# STeaMi-FP12-Capteur_interne.net
KiCad netlist of a schematic drawn in Altium Designer
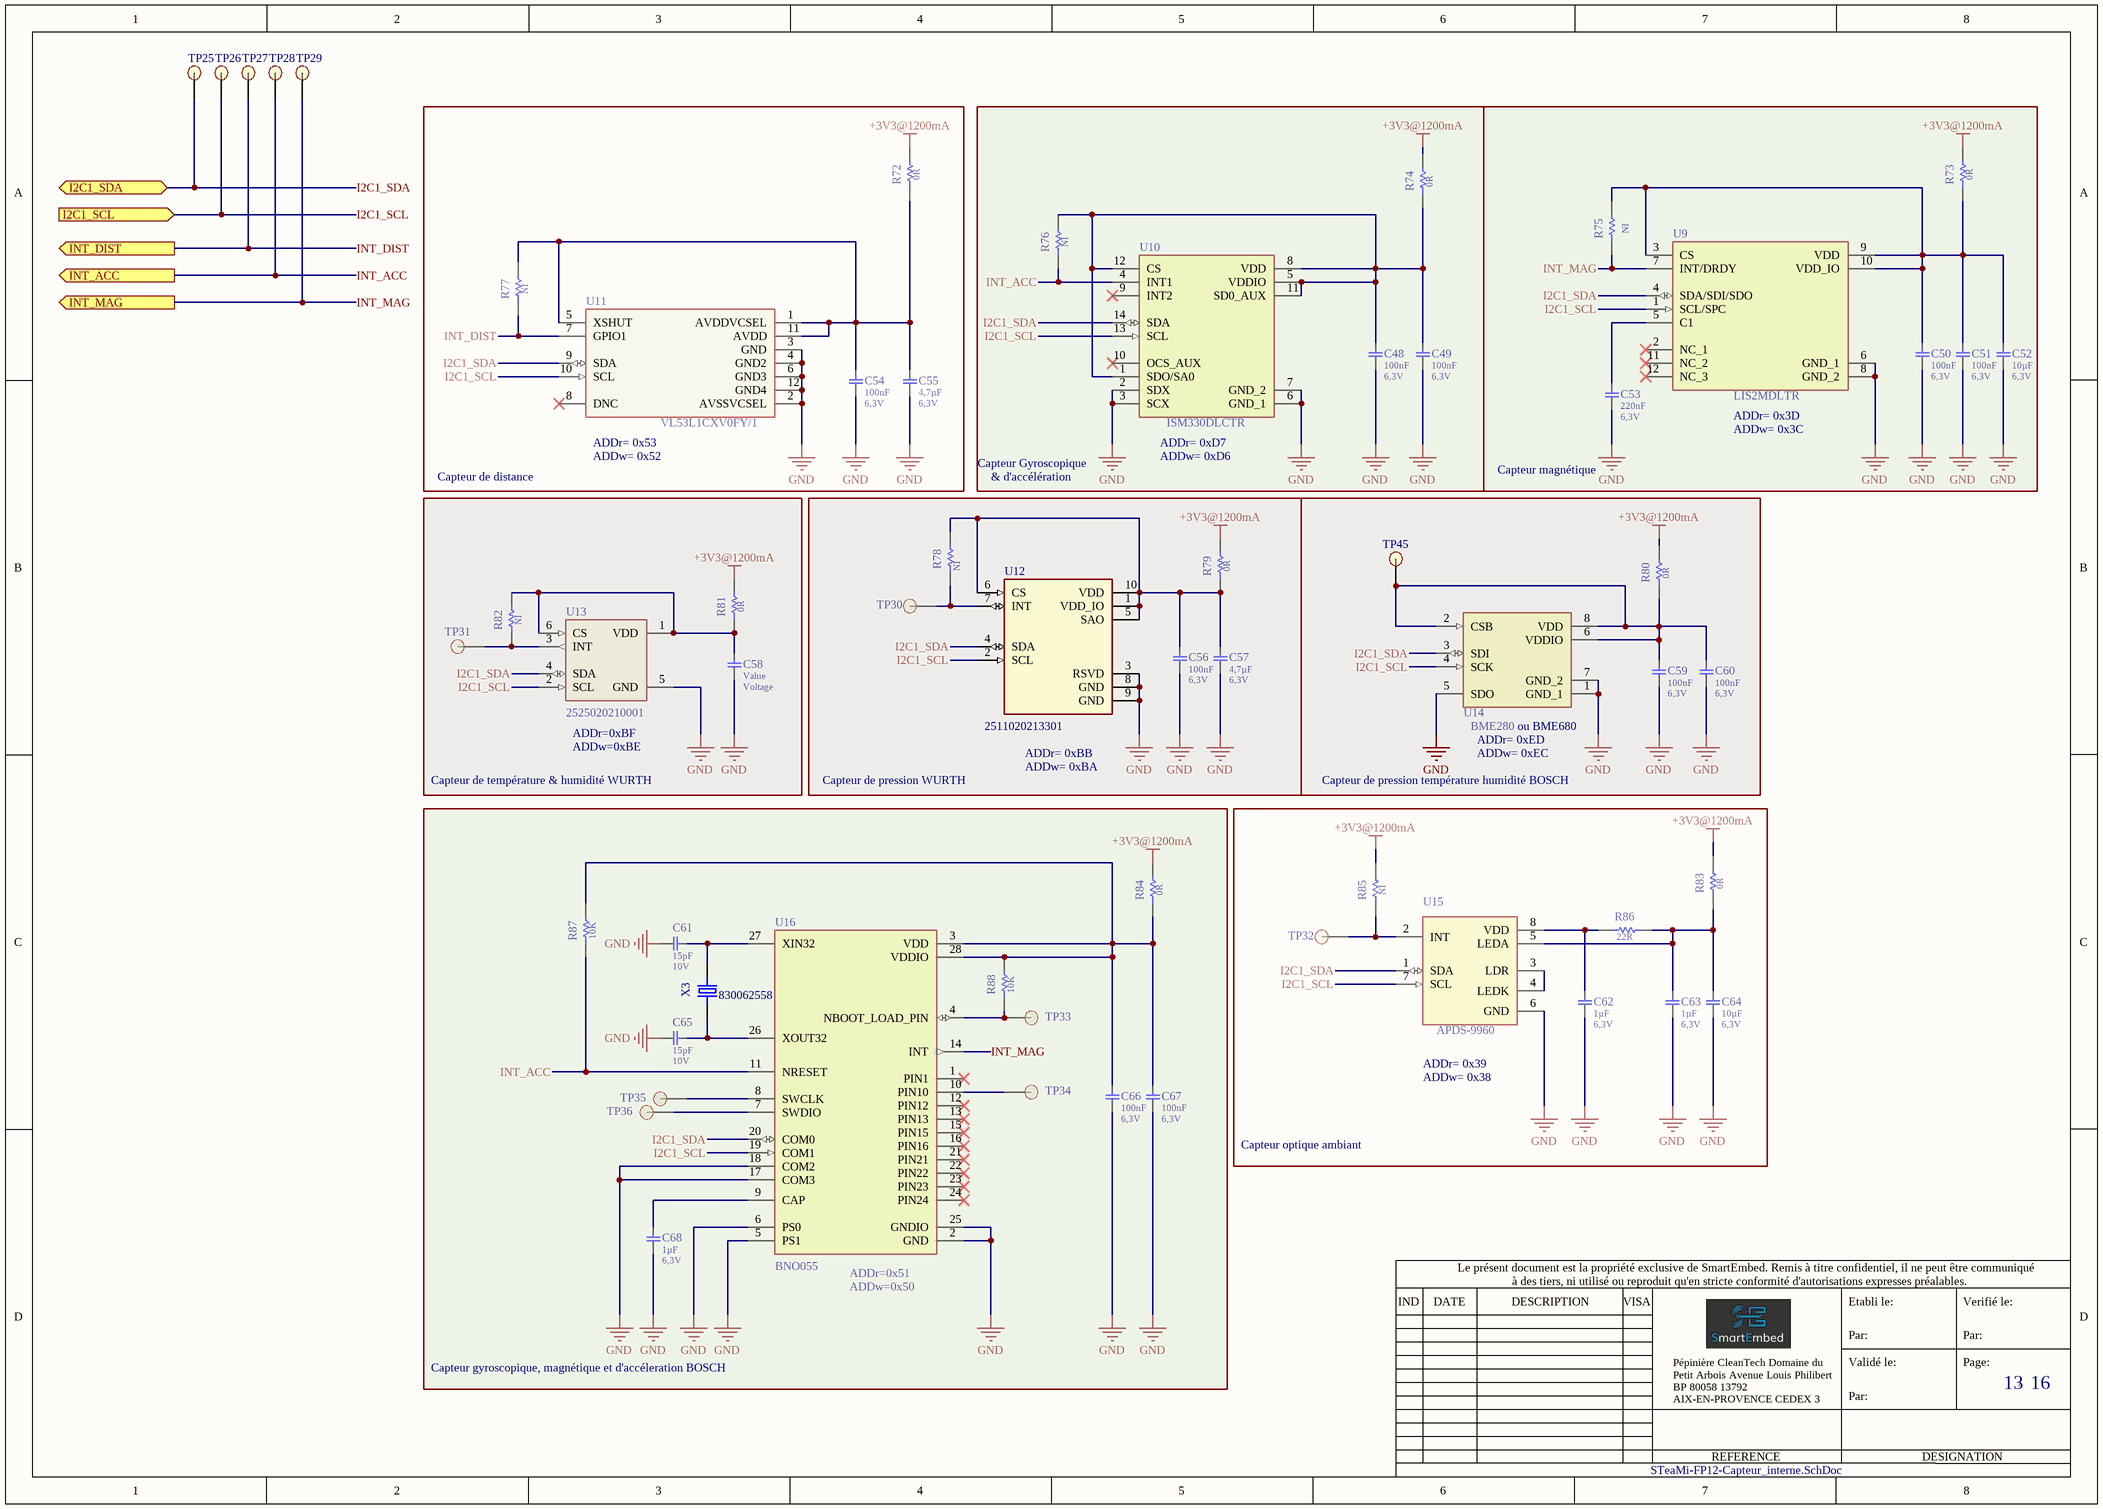
[diagram p0: STeaMi-FP12-Capteur_interne.SchDoc]

(export (version "E")
  (design (tool "Eeschema 10.0.6"))
  (components
    (comp (ref "C48")
      (value "~")
      (footprint "0402-CAP")
      (description "CAP CER 100nF 6,3V X5R 0402")
      (fields
        (field (name "MANUFACTURER") "Kyocera AVX")
        (field (name "MANUFACTURER PART NUMBER") "0402YD104KAT2A")
        (field (name "CAPACITANCE") "100nF")
        (field (name "VOLTAGE") "6,3V")
        (field (name "CREATED BY") "EAG")
        (field (name "CHECKED BY") "*")
      )
      (libsource (lib "ComponentDB") (part "CAP_SYMBOL"))
    )
    (comp (ref "C49")
      (value "~")
      (footprint "0402-CAP")
      (description "CAP CER 100nF 6,3V X5R 0402")
      (fields
        (field (name "MANUFACTURER") "Kyocera AVX")
        (field (name "MANUFACTURER PART NUMBER") "0402YD104KAT2A")
        (field (name "CAPACITANCE") "100nF")
        (field (name "VOLTAGE") "6,3V")
        (field (name "CREATED BY") "EAG")
        (field (name "CHECKED BY") "*")
      )
      (libsource (lib "ComponentDB") (part "CAP_SYMBOL"))
    )
    (comp (ref "C50")
      (value "~")
      (footprint "0402-CAP")
      (description "CAP CER 100nF 6,3V X5R 0402")
      (fields
        (field (name "MANUFACTURER") "Kyocera AVX")
        (field (name "MANUFACTURER PART NUMBER") "0402YD104KAT2A")
        (field (name "CAPACITANCE") "100nF")
        (field (name "VOLTAGE") "6,3V")
        (field (name "CREATED BY") "EAG")
        (field (name "CHECKED BY") "*")
      )
      (libsource (lib "ComponentDB") (part "CAP_SYMBOL"))
    )
    (comp (ref "C51")
      (value "~")
      (footprint "0402-CAP")
      (description "CAP CER 100nF 6,3V X5R 0402")
      (fields
        (field (name "MANUFACTURER") "Kyocera AVX")
        (field (name "MANUFACTURER PART NUMBER") "0402YD104KAT2A")
        (field (name "CAPACITANCE") "100nF")
        (field (name "VOLTAGE") "6,3V")
        (field (name "CREATED BY") "EAG")
        (field (name "CHECKED BY") "*")
      )
      (libsource (lib "ComponentDB") (part "CAP_SYMBOL"))
    )
    (comp (ref "C52")
      (value "~")
      (footprint "0402-CAP")
      (description "CAP CER 10µF 6,3V X5R 0402")
      (fields
        (field (name "MANUFACTURER") "Murata")
        (field (name "MANUFACTURER PART NUMBER") "GRM155R60J106ME15D")
        (field (name "CAPACITANCE") "10µF")
        (field (name "VOLTAGE") "6,3V")
        (field (name "CREATED BY") "EAG")
        (field (name "CHECKED BY") "*")
      )
      (libsource (lib "ComponentDB") (part "CAP_SYMBOL"))
    )
    (comp (ref "C53")
      (value "~")
      (footprint "0603-CAP-Small")
      (description "CAP CER 220nF 6,3V X7R 0603")
      (fields
        (field (name "CAPACITANCE") "220nF")
        (field (name "VOLTAGE") "6,3V")
        (field (name "PART NUMBER") "220nF-10%-6,3V-X7R-0603")
        (field (name "CREATED BY") "EAG")
        (field (name "CHECKED BY") "*")
      )
      (libsource (lib "ComponentDB") (part "CAP_SYMBOL"))
    )
    (comp (ref "C54")
      (value "~")
      (footprint "0402-CAP")
      (description "CAP CER 100nF 6,3V X5R 0402")
      (fields
        (field (name "MANUFACTURER") "Kyocera AVX")
        (field (name "MANUFACTURER PART NUMBER") "0402YD104KAT2A")
        (field (name "CAPACITANCE") "100nF")
        (field (name "VOLTAGE") "6,3V")
        (field (name "CREATED BY") "EAG")
        (field (name "CHECKED BY") "*")
      )
      (libsource (lib "ComponentDB") (part "CAP_SYMBOL"))
    )
    (comp (ref "C55")
      (value "~")
      (footprint "0402-CAP")
      (description "CAP CER 4,7µF 6,3V X5R 0402")
      (fields
        (field (name "CAPACITANCE") "4,7µF")
        (field (name "VOLTAGE") "6,3V")
        (field (name "PART NUMBER") "4,7µF-20%-6,3V-X5R-0402")
        (field (name "CREATED BY") "EAG")
        (field (name "CHECKED BY") "*")
      )
      (libsource (lib "ComponentDB") (part "CAP_SYMBOL"))
    )
    (comp (ref "C56")
      (value "~")
      (footprint "0402-CAP")
      (description "CAP CER 100nF 6,3V X5R 0402")
      (fields
        (field (name "MANUFACTURER") "Kyocera AVX")
        (field (name "MANUFACTURER PART NUMBER") "0402YD104KAT2A")
        (field (name "CAPACITANCE") "100nF")
        (field (name "VOLTAGE") "6,3V")
        (field (name "CREATED BY") "EAG")
        (field (name "CHECKED BY") "*")
      )
      (libsource (lib "ComponentDB") (part "CAP_SYMBOL"))
    )
    (comp (ref "C57")
      (value "~")
      (footprint "0402-CAP")
      (description "CAP CER 4,7µF 6,3V X5R 0402")
      (fields
        (field (name "CAPACITANCE") "4,7µF")
        (field (name "VOLTAGE") "6,3V")
        (field (name "PART NUMBER") "4,7µF-20%-6,3V-X5R-0402")
        (field (name "CREATED BY") "EAG")
        (field (name "CHECKED BY") "*")
      )
      (libsource (lib "ComponentDB") (part "CAP_SYMBOL"))
    )
    (comp (ref "C58")
      (value "~")
      (footprint "0402-CAP")
      (description "CAP CER 100nF 6,3V X5R 0402")
      (fields
        (field (name "CAPACITANCE") "Value")
        (field (name "VOLTAGE") "Voltage")
        (field (name "PART NUMBER") "100nF-10%-6,3V-X5R-0402")
        (field (name "CREATED BY") "*")
        (field (name "CHECKED BY") "*")
      )
      (libsource (lib "ComponentDB") (part "CAP_SYMBOL"))
    )
    (comp (ref "C59")
      (value "~")
      (footprint "0402-CAP")
      (description "CAP CER 100nF 6,3V X5R 0402")
      (fields
        (field (name "MANUFACTURER") "Kyocera AVX")
        (field (name "MANUFACTURER PART NUMBER") "0402YD104KAT2A")
        (field (name "CAPACITANCE") "100nF")
        (field (name "VOLTAGE") "6,3V")
        (field (name "CREATED BY") "EAG")
        (field (name "CHECKED BY") "*")
      )
      (libsource (lib "ComponentDB") (part "CAP_SYMBOL"))
    )
    (comp (ref "C60")
      (value "~")
      (footprint "0402-CAP")
      (description "CAP CER 100nF 6,3V X5R 0402")
      (fields
        (field (name "MANUFACTURER") "Kyocera AVX")
        (field (name "MANUFACTURER PART NUMBER") "0402YD104KAT2A")
        (field (name "CAPACITANCE") "100nF")
        (field (name "VOLTAGE") "6,3V")
        (field (name "CREATED BY") "EAG")
        (field (name "CHECKED BY") "*")
      )
      (libsource (lib "ComponentDB") (part "CAP_SYMBOL"))
    )
    (comp (ref "C61")
      (value "~")
      (footprint "0402-CAP")
      (description "CAP CER 15pF 10V C0G 0402")
      (fields
        (field (name "MANUFACTURER") "KEMET")
        (field (name "MANUFACTURER PART NUMBER") "C0402C150J8HACTU")
        (field (name "CAPACITANCE") "15pF")
        (field (name "VOLTAGE") "10V")
        (field (name "CREATED BY") "EAG")
        (field (name "CHECKED BY") "*")
      )
      (libsource (lib "ComponentDB") (part "CAP_SYMBOL"))
    )
    (comp (ref "C62")
      (value "~")
      (footprint "0402-CAP")
      (description "CAP CER 1µF 6,3V X5R 0402")
      (fields
        (field (name "MANUFACTURER") "Taiyo Yuden")
        (field (name "MANUFACTURER PART NUMBER") "JMK105BJ105KV-F")
        (field (name "CAPACITANCE") "1µF")
        (field (name "VOLTAGE") "6,3V")
        (field (name "CREATED BY") "EAG")
        (field (name "CHECKED BY") "*")
      )
      (libsource (lib "ComponentDB") (part "CAP_SYMBOL"))
    )
    (comp (ref "C63")
      (value "~")
      (footprint "0402-CAP")
      (description "CAP CER 1µF 6,3V X5R 0402")
      (fields
        (field (name "MANUFACTURER") "Taiyo Yuden")
        (field (name "MANUFACTURER PART NUMBER") "JMK105BJ105KV-F")
        (field (name "CAPACITANCE") "1µF")
        (field (name "VOLTAGE") "6,3V")
        (field (name "CREATED BY") "EAG")
        (field (name "CHECKED BY") "*")
      )
      (libsource (lib "ComponentDB") (part "CAP_SYMBOL"))
    )
    (comp (ref "C64")
      (value "~")
      (footprint "0402-CAP")
      (description "CAP CER 10µF 6,3V X5R 0402")
      (fields
        (field (name "MANUFACTURER") "Murata")
        (field (name "MANUFACTURER PART NUMBER") "GRM155R60J106ME15D")
        (field (name "CAPACITANCE") "10µF")
        (field (name "VOLTAGE") "6,3V")
        (field (name "CREATED BY") "EAG")
        (field (name "CHECKED BY") "*")
      )
      (libsource (lib "ComponentDB") (part "CAP_SYMBOL"))
    )
    (comp (ref "C65")
      (value "~")
      (footprint "0402-CAP")
      (description "CAP CER 15pF 10V C0G 0402")
      (fields
        (field (name "MANUFACTURER") "KEMET")
        (field (name "MANUFACTURER PART NUMBER") "C0402C150J8HACTU")
        (field (name "CAPACITANCE") "15pF")
        (field (name "VOLTAGE") "10V")
        (field (name "CREATED BY") "EAG")
        (field (name "CHECKED BY") "*")
      )
      (libsource (lib "ComponentDB") (part "CAP_SYMBOL"))
    )
    (comp (ref "C66")
      (value "~")
      (footprint "0402-CAP")
      (description "CAP CER 100nF 6,3V X5R 0402")
      (fields
        (field (name "MANUFACTURER") "Kyocera AVX")
        (field (name "MANUFACTURER PART NUMBER") "0402YD104KAT2A")
        (field (name "CAPACITANCE") "100nF")
        (field (name "VOLTAGE") "6,3V")
        (field (name "CREATED BY") "EAG")
        (field (name "CHECKED BY") "*")
      )
      (libsource (lib "ComponentDB") (part "CAP_SYMBOL"))
    )
    (comp (ref "C67")
      (value "~")
      (footprint "0402-CAP")
      (description "CAP CER 100nF 6,3V X5R 0402")
      (fields
        (field (name "MANUFACTURER") "Kyocera AVX")
        (field (name "MANUFACTURER PART NUMBER") "0402YD104KAT2A")
        (field (name "CAPACITANCE") "100nF")
        (field (name "VOLTAGE") "6,3V")
        (field (name "CREATED BY") "EAG")
        (field (name "CHECKED BY") "*")
      )
      (libsource (lib "ComponentDB") (part "CAP_SYMBOL"))
    )
    (comp (ref "C68")
      (value "~")
      (footprint "0402-CAP")
      (description "CAP CER 1µF 6,3V X5R 0402")
      (fields
        (field (name "MANUFACTURER") "Taiyo Yuden")
        (field (name "MANUFACTURER PART NUMBER") "JMK105BJ105KV-F")
        (field (name "CAPACITANCE") "1µF")
        (field (name "VOLTAGE") "6,3V")
        (field (name "CREATED BY") "EAG")
        (field (name "CHECKED BY") "*")
      )
      (libsource (lib "ComponentDB") (part "CAP_SYMBOL"))
    )
    (comp (ref "R72")
      (value "~")
      (footprint "RESC1005X40N_0402")
      (description "RES CMS 0R5%-0,0625W-0402")
      (fields
        (field (name "MANUFACTURER") "Yageo")
        (field (name "MANUFACTURER PART NUMBER") "RC0402JR-100RL")
        (field (name "RESISTANCE") "0R")
        (field (name "CREATED BY") "EAG")
      )
      (libsource (lib "ComponentDB") (part "RES_SYMBOL"))
    )
    (comp (ref "R73")
      (value "~")
      (footprint "RESC1005X40N_0402")
      (description "RES CMS 0R5%-0,0625W-0402")
      (fields
        (field (name "MANUFACTURER") "Yageo")
        (field (name "MANUFACTURER PART NUMBER") "RC0402JR-100RL")
        (field (name "RESISTANCE") "0R")
        (field (name "CREATED BY") "EAG")
      )
      (libsource (lib "ComponentDB") (part "RES_SYMBOL"))
    )
    (comp (ref "R74")
      (value "~")
      (footprint "RESC1005X40N_0402")
      (description "RES CMS 0R5%-0,0625W-0402")
      (fields
        (field (name "MANUFACTURER") "Yageo")
        (field (name "MANUFACTURER PART NUMBER") "RC0402JR-100RL")
        (field (name "RESISTANCE") "0R")
        (field (name "CREATED BY") "EAG")
      )
      (libsource (lib "ComponentDB") (part "RES_SYMBOL"))
    )
    (comp (ref "R75")
      (value "~")
      (footprint "RESC1005X40N_0402")
      (description "NI")
      (fields
        (field (name "POWER") "0,1")
        (field (name "RESISTANCE") "NI")
        (field (name "PART NUMBER") "NI-1%-0,1W-0603")
        (field (name "CREATED BY") "MSA")
      )
      (libsource (lib "ComponentDB") (part "RES_SYMBOL"))
    )
    (comp (ref "R76")
      (value "~")
      (footprint "RESC1005X40N_0402")
      (description "NI")
      (fields
        (field (name "POWER") "0,1")
        (field (name "RESISTANCE") "NI")
        (field (name "PART NUMBER") "NI-1%-0,1W-0603")
        (field (name "CREATED BY") "MSA")
      )
      (libsource (lib "ComponentDB") (part "RES_SYMBOL"))
    )
    (comp (ref "R77")
      (value "~")
      (footprint "RESC1005X40N_0402")
      (description "NI")
      (fields
        (field (name "POWER") "0,1")
        (field (name "RESISTANCE") "NI")
        (field (name "PART NUMBER") "NI-1%-0,1W-0603")
        (field (name "CREATED BY") "MSA")
      )
      (libsource (lib "ComponentDB") (part "RES_SYMBOL"))
    )
    (comp (ref "R78")
      (value "~")
      (footprint "RESC1005X40N_0402")
      (description "NI")
      (fields
        (field (name "POWER") "0,1")
        (field (name "RESISTANCE") "NI")
        (field (name "PART NUMBER") "NI-1%-0,1W-0603")
        (field (name "CREATED BY") "MSA")
      )
      (libsource (lib "ComponentDB") (part "RES_SYMBOL"))
    )
    (comp (ref "R79")
      (value "~")
      (footprint "RESC1005X40N_0402")
      (description "RES CMS 0R5%-0,0625W-0402")
      (fields
        (field (name "MANUFACTURER") "Yageo")
        (field (name "MANUFACTURER PART NUMBER") "RC0402JR-100RL")
        (field (name "RESISTANCE") "0R")
        (field (name "CREATED BY") "EAG")
      )
      (libsource (lib "ComponentDB") (part "RES_SYMBOL"))
    )
    (comp (ref "R80")
      (value "~")
      (footprint "RESC1005X40N_0402")
      (description "RES CMS 0R5%-0,0625W-0402")
      (fields
        (field (name "MANUFACTURER") "Yageo")
        (field (name "MANUFACTURER PART NUMBER") "RC0402JR-100RL")
        (field (name "RESISTANCE") "0R")
        (field (name "CREATED BY") "EAG")
      )
      (libsource (lib "ComponentDB") (part "RES_SYMBOL"))
    )
    (comp (ref "R81")
      (value "~")
      (footprint "RESC1608X45N_0603")
      (description "RES CMS 0R 1% 0,1W 0603 ±100ppm/°C")
      (fields
        (field (name "MANUFACTURER") "Vishay")
        (field (name "MANUFACTURER PART NUMBER") "CRCW06030000Z0EAC")
        (field (name "RESISTANCE") "0R")
        (field (name "CREATED BY") "MSA")
      )
      (libsource (lib "ComponentDB") (part "RES_SYMBOL"))
    )
    (comp (ref "R82")
      (value "~")
      (footprint "RESC1608X45N_0603")
      (description "NI")
      (fields
        (field (name "POWER") "0,1")
        (field (name "RESISTANCE") "NI")
        (field (name "PART NUMBER") "NI-1%-0,1W-0603")
        (field (name "CREATED BY") "MSA")
      )
      (libsource (lib "ComponentDB") (part "RES_SYMBOL"))
    )
    (comp (ref "R83")
      (value "~")
      (footprint "RESC1005X40N_0402")
      (description "RES CMS 0R5%-0,0625W-0402")
      (fields
        (field (name "MANUFACTURER") "Yageo")
        (field (name "MANUFACTURER PART NUMBER") "RC0402JR-100RL")
        (field (name "RESISTANCE") "0R")
        (field (name "CREATED BY") "EAG")
      )
      (libsource (lib "ComponentDB") (part "RES_SYMBOL"))
    )
    (comp (ref "R84")
      (value "~")
      (footprint "RESC1005X40N_0402")
      (description "RES CMS 0R5%-0,0625W-0402")
      (fields
        (field (name "MANUFACTURER") "Yageo")
        (field (name "MANUFACTURER PART NUMBER") "RC0402JR-100RL")
        (field (name "RESISTANCE") "0R")
        (field (name "CREATED BY") "EAG")
      )
      (libsource (lib "ComponentDB") (part "RES_SYMBOL"))
    )
    (comp (ref "R85")
      (value "~")
      (footprint "RESC1005X40N_0402")
      (description "NI")
      (fields
        (field (name "POWER") "0,1")
        (field (name "RESISTANCE") "NI")
        (field (name "PART NUMBER") "NI-1%-0,1W-0603")
        (field (name "CREATED BY") "MSA")
      )
      (libsource (lib "ComponentDB") (part "RES_SYMBOL"))
    )
    (comp (ref "R86")
      (value "~")
      (footprint "RESC1005X40N_0402")
      (description "RES CMS 22R0,5%-0,0625W-0402 ±100ppm/°C")
      (fields
        (field (name "MANUFACTURER") "Panasonic")
        (field (name "MANUFACTURER PART NUMBER") "ERJ2RKD22R0X")
        (field (name "RESISTANCE") "22R")
        (field (name "CREATED BY") "EAG")
      )
      (libsource (lib "ComponentDB") (part "RES_SYMBOL"))
    )
    (comp (ref "R87")
      (value "~")
      (footprint "RESC1005X40N_0402")
      (description "RES CMS 10K1%-0,0625W-0402 ±100ppm/°C")
      (fields
        (field (name "MANUFACTURER") "Yageo")
        (field (name "MANUFACTURER PART NUMBER") "AC0402FR-1310KL")
        (field (name "RESISTANCE") "10K")
        (field (name "CREATED BY") "EAG")
      )
      (libsource (lib "ComponentDB") (part "RES_SYMBOL"))
    )
    (comp (ref "R88")
      (value "~")
      (footprint "RESC1005X40N_0402")
      (description "RES CMS 10K1%-0,0625W-0402 ±100ppm/°C")
      (fields
        (field (name "MANUFACTURER") "Yageo")
        (field (name "MANUFACTURER PART NUMBER") "AC0402FR-1310KL")
        (field (name "RESISTANCE") "10K")
        (field (name "CREATED BY") "EAG")
      )
      (libsource (lib "ComponentDB") (part "RES_SYMBOL"))
    )
    (comp (ref "TP25")
      (value "SDA1")
      (footprint "Testpoint 1mm")
      (description "TESTPOINTPAD")
      (fields
        (field (name "MANUFACTURER") "Smartembed")
        (field (name "MANUFACTURER PART NUMBER") "TESTPOINT")
        (field (name "CREATED BY") "EAG")
      )
      (libsource (lib "ComponentDB") (part "TESTPOINT"))
    )
    (comp (ref "TP26")
      (value "SCL1")
      (footprint "Testpoint 1mm")
      (description "TESTPOINTPAD")
      (fields
        (field (name "MANUFACTURER") "Smartembed")
        (field (name "MANUFACTURER PART NUMBER") "TESTPOINT")
        (field (name "CREATED BY") "EAG")
      )
      (libsource (lib "ComponentDB") (part "TESTPOINT"))
    )
    (comp (ref "TP27")
      (value "INTD")
      (footprint "Testpoint 1mm")
      (description "TESTPOINTPAD")
      (fields
        (field (name "MANUFACTURER") "Smartembed")
        (field (name "MANUFACTURER PART NUMBER") "TESTPOINT")
        (field (name "CREATED BY") "EAG")
      )
      (libsource (lib "ComponentDB") (part "TESTPOINT"))
    )
    (comp (ref "TP28")
      (value "INTA")
      (footprint "Testpoint 1mm")
      (description "TESTPOINTPAD")
      (fields
        (field (name "MANUFACTURER") "Smartembed")
        (field (name "MANUFACTURER PART NUMBER") "TESTPOINT")
        (field (name "CREATED BY") "EAG")
      )
      (libsource (lib "ComponentDB") (part "TESTPOINT"))
    )
    (comp (ref "TP29")
      (value "INTM")
      (footprint "Testpoint 1mm")
      (description "TESTPOINTPAD")
      (fields
        (field (name "MANUFACTURER") "Smartembed")
        (field (name "MANUFACTURER PART NUMBER") "TESTPOINT")
        (field (name "CREATED BY") "EAG")
      )
      (libsource (lib "ComponentDB") (part "TESTPOINT"))
    )
    (comp (ref "TP30")
      (value "PAD")
      (footprint "Testpoint 1mm")
      (description "TESTPOINTPAD")
      (fields
        (field (name "MANUFACTURER") "Smartembed")
        (field (name "MANUFACTURER PART NUMBER") "TESTPOINT")
        (field (name "CREATED BY") "EAG")
      )
      (libsource (lib "ComponentDB") (part "TESTPOINT"))
    )
    (comp (ref "TP31")
      (value "PAD")
      (footprint "Testpoint 1mm")
      (description "TESTPOINTPAD")
      (fields
        (field (name "MANUFACTURER") "Smartembed")
        (field (name "MANUFACTURER PART NUMBER") "TESTPOINT")
        (field (name "CREATED BY") "EAG")
      )
      (libsource (lib "ComponentDB") (part "TESTPOINT"))
    )
    (comp (ref "TP32")
      (value "PAD")
      (footprint "Testpoint 1mm")
      (description "TESTPOINTPAD")
      (fields
        (field (name "MANUFACTURER") "Smartembed")
        (field (name "MANUFACTURER PART NUMBER") "TESTPOINT")
        (field (name "CREATED BY") "EAG")
      )
      (libsource (lib "ComponentDB") (part "TESTPOINT"))
    )
    (comp (ref "TP33")
      (value "PAD")
      (footprint "Testpoint 1mm")
      (description "TESTPOINTPAD")
      (fields
        (field (name "MANUFACTURER") "Smartembed")
        (field (name "MANUFACTURER PART NUMBER") "TESTPOINT")
        (field (name "CREATED BY") "EAG")
      )
      (libsource (lib "ComponentDB") (part "TESTPOINT"))
    )
    (comp (ref "TP34")
      (value "PAD")
      (footprint "Testpoint 1mm")
      (description "TESTPOINTPAD")
      (fields
        (field (name "MANUFACTURER") "Smartembed")
        (field (name "MANUFACTURER PART NUMBER") "TESTPOINT")
        (field (name "CREATED BY") "EAG")
      )
      (libsource (lib "ComponentDB") (part "TESTPOINT"))
    )
    (comp (ref "TP35")
      (value "PAD")
      (footprint "Testpoint 1mm")
      (description "TESTPOINTPAD")
      (fields
        (field (name "MANUFACTURER") "Smartembed")
        (field (name "MANUFACTURER PART NUMBER") "TESTPOINT")
        (field (name "CREATED BY") "EAG")
      )
      (libsource (lib "ComponentDB") (part "TESTPOINT"))
    )
    (comp (ref "TP36")
      (value "PAD")
      (footprint "Testpoint 1mm")
      (description "TESTPOINTPAD")
      (fields
        (field (name "MANUFACTURER") "Smartembed")
        (field (name "MANUFACTURER PART NUMBER") "TESTPOINT")
        (field (name "CREATED BY") "EAG")
      )
      (libsource (lib "ComponentDB") (part "TESTPOINT"))
    )
    (comp (ref "TP45")
      (value "PAD")
      (footprint "Testpoint 1mm")
      (description "TESTPOINTPAD")
      (fields (field (name "MANUFACTURER") "SmartEmbed"))
      (libsource (lib "ComponentDB") (part "TESTPOINT"))
    )
    (comp (ref "U9")
      (value "~")
      (footprint "LGA-12-2x2MM")
      (description "magnétorésistif Capteur X, Y, Z axe 12-LGA (2x2)")
      (fields
        (field (name "MANUFACTURER") "STMicroelectronics")
        (field (name "MANUFACTURER PART NUMBER") "LIS2MDLTR")
        (field (name "PART NUMBER") "LIS2MDLTR")
        (field (name "CREATED BY") "EAG")
        (field (name "CHECKED BY") "*")
      )
      (libsource (lib "ComponentDB") (part "LIS2MDLTR"))
    )
    (comp (ref "U10")
      (value "~")
      (footprint "LGA-14-2.5X3MM")
      (description "Accéléromètre, gyroscope, température, 6 axes Anturi I²C, SPI Sortie")
      (fields
        (field (name "MANUFACTURER") "STMicroelectronics")
        (field (name "MANUFACTURER PART NUMBER") "ISM330DLCTR")
        (field (name "PART NUMBER") "ISM330DLCTR")
        (field (name "CREATED BY") "EAG")
        (field (name "CHECKED BY") "*")
      )
      (libsource (lib "ComponentDB") (part "ISM330DLCTR"))
    )
    (comp (ref "U11")
      (value "~")
      (footprint "VL53L1X")
      (description "SENSOR OPTICAL 4M I2C")
      (fields
        (field (name "MANUFACTURER") "STMicroelectronics")
        (field (name "MANUFACTURER PART NUMBER") "VL53L1CXV0FY/1")
        (field (name "PART NUMBER") "VL53L1X")
        (field (name "CREATED BY") "EAG")
        (field (name "CHECKED BY") "*")
      )
      (libsource (lib "ComponentDB") (part "VL53L1X"))
    )
    (comp (ref "U12")
      (value "~")
      (footprint "2511020213301")
      (description "Capteur de pression 3,77PSI ~ 18,27PSI (26kPa ~ 126kPa) Absolu  24 b 10-WFLGA")
      (fields
        (field (name "MANUFACTURER") "Wurth Elektronik")
        (field (name "MANUFACTURER PART NUMBER") "2511020213301")
        (field (name "PART NUMBER") "2511020213301")
        (field (name "CREATED BY") "EAG")
        (field (name "CHECKED BY") "*")
      )
      (libsource (lib "ComponentDB") (part "2511020213301"))
    )
    (comp (ref "U13")
      (value "~")
      (footprint "2525020210001")
      (description "Humidité, température Capteur I²C, SPI Sortie")
      (fields
        (field (name "MANUFACTURER") "Wurth Elektronik")
        (field (name "MANUFACTURER PART NUMBER") "2525020210001")
        (field (name "PART NUMBER") "2525020210001")
        (field (name "CREATED BY") "EAG")
        (field (name "CHECKED BY") "*")
      )
      (libsource (lib "ComponentDB") (part "2525020210001"))
    )
    (comp (ref "U14")
      (value "~")
      (footprint "BME280")
      (description "Capteur de température et d'humidité 0 ~ 100 %HR I²C, SPI ±3% 1s Montage en surface")
      (fields
        (field (name "MANUFACTURER") "Bosch")
        (field (name "MANUFACTURER PART NUMBER") "BME280")
        (field (name "PART NUMBER") "BME280")
        (field (name "CREATED BY") "EAG")
        (field (name "CHECKED BY") "*")
      )
      (libsource (lib "ComponentDB") (part "BME280"))
    )
    (comp (ref "U15")
      (value "~")
      (footprint "APDS-9960")
      (description "Capteurs optiques Ambiant 560nm I²C Module 8-SMD")
      (fields
        (field (name "MANUFACTURER") "Broadcom Limited")
        (field (name "MANUFACTURER PART NUMBER") "APDS-9960")
        (field (name "PART NUMBER") "APDS-9960")
        (field (name "CREATED BY") "EAG")
        (field (name "CHECKED BY") "*")
      )
      (libsource (lib "ComponentDB") (part "APDS-9960"))
    )
    (comp (ref "U16")
      (value "~")
      (footprint "LGA28R50P4X10_380X520X100")
      (description "Accéléromètre, gyroscope, magnétomètre, 9 axes Anturi I²C, UART Sortie")
      (fields
        (field (name "MANUFACTURER") "Bosch")
        (field (name "MANUFACTURER PART NUMBER") "BNO055")
        (field (name "PART NUMBER") "BNO055")
        (field (name "CREATED BY") "EAG")
        (field (name "CHECKED BY") "*")
      )
      (libsource (lib "ComponentDB") (part "BNO055"))
    )
    (comp (ref "X3")
      (value "~")
      (footprint "WE_XTAL_IQXC-25")
      (description "QUARTZ 32Khz 12pF 30 ppm")
      (fields
        (field (name "MANUFACTURER PART NUMBER") "830062558")
        (field (name "MANUFACTURER") "Wurth")
        (field (name "PART NUMBER") "830062558")
        (field (name "CREATED BY") "EAG")
      )
      (libsource (lib "ComponentDB") (part "2PIN"))
    )
  )
  (nets
    (net (code "1") (name "+3V3@1200mA") (class "Default")
      (node (ref "R72") (pin "2") (pinfunction "2_2") (pintype "passive"))
      (node (ref "R73") (pin "2") (pinfunction "2_2") (pintype "passive"))
      (node (ref "R74") (pin "2") (pinfunction "2_2") (pintype "passive"))
      (node (ref "R79") (pin "2") (pinfunction "2_2") (pintype "passive"))
      (node (ref "R80") (pin "2") (pinfunction "2_2") (pintype "passive"))
      (node (ref "R81") (pin "2") (pinfunction "2_2") (pintype "passive"))
      (node (ref "R83") (pin "2") (pinfunction "2_2") (pintype "passive"))
      (node (ref "R84") (pin "2") (pinfunction "2_2") (pintype "passive"))
      (node (ref "R85") (pin "2") (pinfunction "2_2") (pintype "passive"))
    )
    (net (code "2") (name "/I2C1_SCL") (class "Default")
      (node (ref "TP26") (pin "1") (pinfunction "1_1") (pintype "passive"))
      (node (ref "U10") (pin "13") (pinfunction "SCL_13") (pintype "input"))
      (node (ref "U11") (pin "10") (pinfunction "SCL_10") (pintype "input"))
      (node (ref "U12") (pin "2") (pinfunction "SCL_2") (pintype "input"))
      (node (ref "U13") (pin "2") (pinfunction "SCL_2") (pintype "input"))
      (node (ref "U14") (pin "4") (pinfunction "SCK_4") (pintype "input"))
      (node (ref "U15") (pin "7") (pinfunction "SCL_7") (pintype "input"))
      (node (ref "U16") (pin "19") (pinfunction "COM1_19") (pintype "input"))
      (node (ref "U9") (pin "1") (pinfunction "SCL/SPC_1") (pintype "input"))
    )
    (net (code "3") (name "/I2C1_SDA") (class "Default")
      (node (ref "TP25") (pin "1") (pinfunction "1_1") (pintype "passive"))
      (node (ref "U10") (pin "14") (pinfunction "SDA_14") (pintype "bidirectional"))
      (node (ref "U11") (pin "9") (pinfunction "SDA_9") (pintype "bidirectional"))
      (node (ref "U12") (pin "4") (pinfunction "SDA_4") (pintype "bidirectional"))
      (node (ref "U13") (pin "4") (pinfunction "SDA_4") (pintype "bidirectional"))
      (node (ref "U14") (pin "3") (pinfunction "SDI_3") (pintype "bidirectional"))
      (node (ref "U15") (pin "1") (pinfunction "SDA_1") (pintype "bidirectional"))
      (node (ref "U16") (pin "20") (pinfunction "COM0_20") (pintype "bidirectional"))
      (node (ref "U9") (pin "4") (pinfunction "SDA/SDI/SDO_4") (pintype "bidirectional"))
    )
    (net (code "4") (name "/INT_ACC") (class "Default")
      (node (ref "R76") (pin "1") (pinfunction "1_1") (pintype "passive"))
      (node (ref "R87") (pin "1") (pinfunction "1_1") (pintype "passive"))
      (node (ref "TP28") (pin "1") (pinfunction "1_1") (pintype "passive"))
      (node (ref "U10") (pin "4") (pinfunction "INT1_4") (pintype "passive"))
      (node (ref "U16") (pin "11") (pinfunction "NRESET_11") (pintype "passive"))
    )
    (net (code "5") (name "/INT_DIST") (class "Default")
      (node (ref "R77") (pin "1") (pinfunction "1_1") (pintype "passive"))
      (node (ref "TP27") (pin "1") (pinfunction "1_1") (pintype "passive"))
      (node (ref "U11") (pin "7") (pinfunction "GPIO1_7") (pintype "passive"))
    )
    (net (code "6") (name "/INT_MAG") (class "Default")
      (node (ref "R75") (pin "1") (pinfunction "1_1") (pintype "passive"))
      (node (ref "TP29") (pin "1") (pinfunction "1_1") (pintype "passive"))
      (node (ref "U16") (pin "14") (pinfunction "INT_14") (pintype "output"))
      (node (ref "U9") (pin "7") (pinfunction "INT/DRDY_7") (pintype "passive"))
    )
    (net (code "7") (name "GND") (class "Default")
      (node (ref "C48") (pin "1") (pinfunction "1_1") (pintype "passive"))
      (node (ref "C49") (pin "1") (pinfunction "1_1") (pintype "passive"))
      (node (ref "C50") (pin "1") (pinfunction "1_1") (pintype "passive"))
      (node (ref "C51") (pin "1") (pinfunction "1_1") (pintype "passive"))
      (node (ref "C52") (pin "1") (pinfunction "1_1") (pintype "passive"))
      (node (ref "C53") (pin "1") (pinfunction "1_1") (pintype "passive"))
      (node (ref "C54") (pin "1") (pinfunction "1_1") (pintype "passive"))
      (node (ref "C55") (pin "1") (pinfunction "1_1") (pintype "passive"))
      (node (ref "C56") (pin "1") (pinfunction "1_1") (pintype "passive"))
      (node (ref "C57") (pin "1") (pinfunction "1_1") (pintype "passive"))
      (node (ref "C58") (pin "1") (pinfunction "1_1") (pintype "passive"))
      (node (ref "C59") (pin "1") (pinfunction "1_1") (pintype "passive"))
      (node (ref "C60") (pin "1") (pinfunction "1_1") (pintype "passive"))
      (node (ref "C61") (pin "1") (pinfunction "1_1") (pintype "passive"))
      (node (ref "C62") (pin "1") (pinfunction "1_1") (pintype "passive"))
      (node (ref "C63") (pin "1") (pinfunction "1_1") (pintype "passive"))
      (node (ref "C64") (pin "1") (pinfunction "1_1") (pintype "passive"))
      (node (ref "C65") (pin "1") (pinfunction "1_1") (pintype "passive"))
      (node (ref "C66") (pin "1") (pinfunction "1_1") (pintype "passive"))
      (node (ref "C67") (pin "1") (pinfunction "1_1") (pintype "passive"))
      (node (ref "C68") (pin "1") (pinfunction "1_1") (pintype "passive"))
      (node (ref "U10") (pin "2") (pinfunction "SDX_2") (pintype "passive"))
      (node (ref "U10") (pin "3") (pinfunction "SCX_3") (pintype "passive"))
      (node (ref "U10") (pin "6") (pinfunction "GND_1_6") (pintype "passive"))
      (node (ref "U10") (pin "7") (pinfunction "GND_2_7") (pintype "passive"))
      (node (ref "U11") (pin "12") (pinfunction "GND4_12") (pintype "passive"))
      (node (ref "U11") (pin "2") (pinfunction "AVSSVCSEL_2") (pintype "passive"))
      (node (ref "U11") (pin "3") (pinfunction "GND_3") (pintype "passive"))
      (node (ref "U11") (pin "4") (pinfunction "GND2_4") (pintype "passive"))
      (node (ref "U11") (pin "6") (pinfunction "GND3_6") (pintype "passive"))
      (node (ref "U12") (pin "3") (pinfunction "RSVD_3") (pintype "passive"))
      (node (ref "U12") (pin "8") (pinfunction "GND_8") (pintype "power_in"))
      (node (ref "U12") (pin "9") (pinfunction "GND_9") (pintype "power_in"))
      (node (ref "U13") (pin "5") (pinfunction "GND_5") (pintype "power_in"))
      (node (ref "U14") (pin "1") (pinfunction "GND_1_1") (pintype "power_in"))
      (node (ref "U14") (pin "5") (pinfunction "SDO_5") (pintype "passive"))
      (node (ref "U14") (pin "7") (pinfunction "GND_2_7") (pintype "power_in"))
      (node (ref "U15") (pin "6") (pinfunction "GND_6") (pintype "passive"))
      (node (ref "U16") (pin "17") (pinfunction "COM3_17") (pintype "passive"))
      (node (ref "U16") (pin "18") (pinfunction "COM2_18") (pintype "passive"))
      (node (ref "U16") (pin "2") (pinfunction "GND_2") (pintype "power_in"))
      (node (ref "U16") (pin "25") (pinfunction "GNDIO_25") (pintype "power_in"))
      (node (ref "U16") (pin "5") (pinfunction "PS1_5") (pintype "passive"))
      (node (ref "U16") (pin "6") (pinfunction "PS0_6") (pintype "passive"))
      (node (ref "U9") (pin "6") (pinfunction "GND_1_6") (pintype "passive"))
      (node (ref "U9") (pin "8") (pinfunction "GND_2_8") (pintype "passive"))
    )
    (net (code "8") (name "Net-(U9-C1)") (class "Default")
      (node (ref "C53") (pin "2") (pinfunction "2_2") (pintype "passive"))
      (node (ref "U9") (pin "5") (pinfunction "C1_5") (pintype "passive"))
    )
    (net (code "9") (name "Net-(U9-CS)") (class "Default")
      (node (ref "C50") (pin "2") (pinfunction "2_2") (pintype "passive"))
      (node (ref "C51") (pin "2") (pinfunction "2_2") (pintype "passive"))
      (node (ref "C52") (pin "2") (pinfunction "2_2") (pintype "passive"))
      (node (ref "R73") (pin "1") (pinfunction "1_1") (pintype "passive"))
      (node (ref "R75") (pin "2") (pinfunction "2_2") (pintype "passive"))
      (node (ref "U9") (pin "10") (pinfunction "VDD_IO_10") (pintype "passive"))
      (node (ref "U9") (pin "3") (pinfunction "CS_3") (pintype "passive"))
      (node (ref "U9") (pin "9") (pinfunction "VDD_9") (pintype "passive"))
    )
    (net (code "10") (name "Net-(U10-CS)") (class "Default")
      (node (ref "C48") (pin "2") (pinfunction "2_2") (pintype "passive"))
      (node (ref "C49") (pin "2") (pinfunction "2_2") (pintype "passive"))
      (node (ref "R74") (pin "1") (pinfunction "1_1") (pintype "passive"))
      (node (ref "R76") (pin "2") (pinfunction "2_2") (pintype "passive"))
      (node (ref "U10") (pin "1") (pinfunction "SDO/SA0_1") (pintype "passive"))
      (node (ref "U10") (pin "11") (pinfunction "SD0_AUX_11") (pintype "passive"))
      (node (ref "U10") (pin "12") (pinfunction "CS_12") (pintype "passive"))
      (node (ref "U10") (pin "5") (pinfunction "VDDIO_5") (pintype "passive"))
      (node (ref "U10") (pin "8") (pinfunction "VDD_8") (pintype "passive"))
    )
    (net (code "11") (name "Net-(U11-AVDD)") (class "Default")
      (node (ref "C54") (pin "2") (pinfunction "2_2") (pintype "passive"))
      (node (ref "C55") (pin "2") (pinfunction "2_2") (pintype "passive"))
      (node (ref "R72") (pin "1") (pinfunction "1_1") (pintype "passive"))
      (node (ref "R77") (pin "2") (pinfunction "2_2") (pintype "passive"))
      (node (ref "U11") (pin "1") (pinfunction "AVDDVCSEL_1") (pintype "passive"))
      (node (ref "U11") (pin "11") (pinfunction "AVDD_11") (pintype "passive"))
      (node (ref "U11") (pin "5") (pinfunction "XSHUT_5") (pintype "passive"))
    )
    (net (code "12") (name "Net-(U12-CS)") (class "Default")
      (node (ref "C56") (pin "2") (pinfunction "2_2") (pintype "passive"))
      (node (ref "C57") (pin "2") (pinfunction "2_2") (pintype "passive"))
      (node (ref "R78") (pin "2") (pinfunction "2_2") (pintype "passive"))
      (node (ref "R79") (pin "1") (pinfunction "1_1") (pintype "passive"))
      (node (ref "U12") (pin "1") (pinfunction "VDD_IO_1") (pintype "power_in"))
      (node (ref "U12") (pin "10") (pinfunction "VDD_10") (pintype "power_in"))
      (node (ref "U12") (pin "5") (pinfunction "SAO_5") (pintype "passive"))
      (node (ref "U12") (pin "6") (pinfunction "CS_6") (pintype "input"))
    )
    (net (code "13") (name "Net-(U12-INT)") (class "Default")
      (node (ref "R78") (pin "1") (pinfunction "1_1") (pintype "passive"))
      (node (ref "TP30") (pin "1") (pinfunction "1_1") (pintype "passive"))
      (node (ref "U12") (pin "7") (pinfunction "INT_7") (pintype "bidirectional"))
    )
    (net (code "14") (name "Net-(U13-CS)") (class "Default")
      (node (ref "C58") (pin "2") (pinfunction "2_2") (pintype "passive"))
      (node (ref "R81") (pin "1") (pinfunction "1_1") (pintype "passive"))
      (node (ref "R82") (pin "2") (pinfunction "2_2") (pintype "passive"))
      (node (ref "U13") (pin "1") (pinfunction "VDD_1") (pintype "power_in"))
      (node (ref "U13") (pin "6") (pinfunction "CS_6") (pintype "input"))
    )
    (net (code "15") (name "Net-(U13-INT)") (class "Default")
      (node (ref "R82") (pin "1") (pinfunction "1_1") (pintype "passive"))
      (node (ref "TP31") (pin "1") (pinfunction "1_1") (pintype "passive"))
      (node (ref "U13") (pin "3") (pinfunction "INT_3") (pintype "output"))
    )
    (net (code "16") (name "Net-(U14-CSB)") (class "Default")
      (node (ref "C59") (pin "2") (pinfunction "2_2") (pintype "passive"))
      (node (ref "C60") (pin "2") (pinfunction "2_2") (pintype "passive"))
      (node (ref "R80") (pin "1") (pinfunction "1_1") (pintype "passive"))
      (node (ref "TP45") (pin "1") (pinfunction "1_1") (pintype "passive"))
      (node (ref "U14") (pin "2") (pinfunction "CSB_2") (pintype "input"))
      (node (ref "U14") (pin "6") (pinfunction "VDDIO_6") (pintype "power_in"))
      (node (ref "U14") (pin "8") (pinfunction "VDD_8") (pintype "power_in"))
    )
    (net (code "17") (name "Net-(U15-INT)") (class "Default")
      (node (ref "R85") (pin "1") (pinfunction "1_1") (pintype "passive"))
      (node (ref "TP32") (pin "1") (pinfunction "1_1") (pintype "passive"))
      (node (ref "U15") (pin "2") (pinfunction "INT_2") (pintype "passive"))
    )
    (net (code "18") (name "Net-(U15-LDR)") (class "Default")
      (node (ref "U15") (pin "3") (pinfunction "LDR_3") (pintype "passive"))
      (node (ref "U15") (pin "4") (pinfunction "LEDK_4") (pintype "passive"))
    )
    (net (code "19") (name "Net-(U15-LEDA)") (class "Default")
      (node (ref "C63") (pin "2") (pinfunction "2_2") (pintype "passive"))
      (node (ref "C64") (pin "2") (pinfunction "2_2") (pintype "passive"))
      (node (ref "R83") (pin "1") (pinfunction "1_1") (pintype "passive"))
      (node (ref "R86") (pin "2") (pinfunction "2_2") (pintype "passive"))
      (node (ref "U15") (pin "5") (pinfunction "LEDA_5") (pintype "passive"))
    )
    (net (code "20") (name "Net-(U15-VDD)") (class "Default")
      (node (ref "C62") (pin "2") (pinfunction "2_2") (pintype "passive"))
      (node (ref "R86") (pin "1") (pinfunction "1_1") (pintype "passive"))
      (node (ref "U15") (pin "8") (pinfunction "VDD_8") (pintype "passive"))
    )
    (net (code "21") (name "Net-(U16-CAP)") (class "Default")
      (node (ref "C68") (pin "2") (pinfunction "2_2") (pintype "passive"))
      (node (ref "U16") (pin "9") (pinfunction "CAP_9") (pintype "passive"))
    )
    (net (code "22") (name "Net-(U16-NBOOT_LOAD_PIN)") (class "Default")
      (node (ref "R88") (pin "1") (pinfunction "1_1") (pintype "passive"))
      (node (ref "TP33") (pin "1") (pinfunction "1_1") (pintype "passive"))
      (node (ref "U16") (pin "4") (pinfunction "NBOOT_LOAD_PIN_4") (pintype "bidirectional"))
    )
    (net (code "23") (name "Net-(U16-PIN10)") (class "Default")
      (node (ref "TP34") (pin "1") (pinfunction "1_1") (pintype "passive"))
      (node (ref "U16") (pin "10") (pinfunction "PIN10_10") (pintype "power_in"))
    )
    (net (code "24") (name "Net-(U16-SWCLK)") (class "Default")
      (node (ref "TP35") (pin "1") (pinfunction "1_1") (pintype "passive"))
      (node (ref "U16") (pin "8") (pinfunction "SWCLK_8") (pintype "passive"))
    )
    (net (code "25") (name "Net-(U16-SWDIO)") (class "Default")
      (node (ref "TP36") (pin "1") (pinfunction "1_1") (pintype "passive"))
      (node (ref "U16") (pin "7") (pinfunction "SWDIO_7") (pintype "passive"))
    )
    (net (code "26") (name "Net-(U16-VDD)") (class "Default")
      (node (ref "C66") (pin "2") (pinfunction "2_2") (pintype "passive"))
      (node (ref "C67") (pin "2") (pinfunction "2_2") (pintype "passive"))
      (node (ref "R84") (pin "1") (pinfunction "1_1") (pintype "passive"))
      (node (ref "R87") (pin "2") (pinfunction "2_2") (pintype "passive"))
      (node (ref "R88") (pin "2") (pinfunction "2_2") (pintype "passive"))
      (node (ref "U16") (pin "28") (pinfunction "VDDIO_28") (pintype "power_in"))
      (node (ref "U16") (pin "3") (pinfunction "VDD_3") (pintype "power_in"))
    )
    (net (code "27") (name "Net-(U16-XIN32)") (class "Default")
      (node (ref "C61") (pin "2") (pinfunction "2_2") (pintype "passive"))
      (node (ref "U16") (pin "27") (pinfunction "XIN32_27") (pintype "passive"))
      (node (ref "X3") (pin "2") (pinfunction "2_2") (pintype "passive"))
    )
    (net (code "28") (name "Net-(U16-XOUT32)") (class "Default")
      (node (ref "C65") (pin "2") (pinfunction "2_2") (pintype "passive"))
      (node (ref "U16") (pin "26") (pinfunction "XOUT32_26") (pintype "passive"))
      (node (ref "X3") (pin "1") (pinfunction "1_1") (pintype "passive"))
    )
    (net (code "29") (name "unconnected-(U9-NC_1-Pad2)") (class "Default")
      (node (ref "U9") (pin "2") (pinfunction "NC_1_2") (pintype "passive+no_connect"))
    )
    (net (code "30") (name "unconnected-(U9-NC_2-Pad11)") (class "Default")
      (node (ref "U9") (pin "11") (pinfunction "NC_2_11") (pintype "passive+no_connect"))
    )
    (net (code "31") (name "unconnected-(U9-NC_3-Pad12)") (class "Default")
      (node (ref "U9") (pin "12") (pinfunction "NC_3_12") (pintype "passive+no_connect"))
    )
    (net (code "32") (name "unconnected-(U10-INT2-Pad9)") (class "Default")
      (node (ref "U10") (pin "9") (pinfunction "INT2_9") (pintype "passive+no_connect"))
    )
    (net (code "33") (name "unconnected-(U10-OCS_AUX-Pad10)") (class "Default")
      (node (ref "U10") (pin "10") (pinfunction "OCS_AUX_10") (pintype "passive+no_connect"))
    )
    (net (code "34") (name "unconnected-(U11-DNC-Pad8)") (class "Default")
      (node (ref "U11") (pin "8") (pinfunction "DNC_8") (pintype "passive+no_connect"))
    )
    (net (code "35") (name "unconnected-(U16-PIN1-Pad1)") (class "Default")
      (node (ref "U16") (pin "1") (pinfunction "PIN1_1") (pintype "passive+no_connect"))
    )
    (net (code "36") (name "unconnected-(U16-PIN12-Pad12)") (class "Default")
      (node (ref "U16") (pin "12") (pinfunction "PIN12_12") (pintype "passive+no_connect"))
    )
    (net (code "37") (name "unconnected-(U16-PIN13-Pad13)") (class "Default")
      (node (ref "U16") (pin "13") (pinfunction "PIN13_13") (pintype "passive+no_connect"))
    )
    (net (code "38") (name "unconnected-(U16-PIN15-Pad15)") (class "Default")
      (node (ref "U16") (pin "15") (pinfunction "PIN15_15") (pintype "power_in+no_connect"))
    )
    (net (code "39") (name "unconnected-(U16-PIN16-Pad16)") (class "Default")
      (node (ref "U16") (pin "16") (pinfunction "PIN16_16") (pintype "power_in+no_connect"))
    )
    (net (code "40") (name "unconnected-(U16-PIN21-Pad21)") (class "Default")
      (node (ref "U16") (pin "21") (pinfunction "PIN21_21") (pintype "passive+no_connect"))
    )
    (net (code "41") (name "unconnected-(U16-PIN22-Pad22)") (class "Default")
      (node (ref "U16") (pin "22") (pinfunction "PIN22_22") (pintype "passive+no_connect"))
    )
    (net (code "42") (name "unconnected-(U16-PIN23-Pad23)") (class "Default")
      (node (ref "U16") (pin "23") (pinfunction "PIN23_23") (pintype "passive+no_connect"))
    )
    (net (code "43") (name "unconnected-(U16-PIN24-Pad24)") (class "Default")
      (node (ref "U16") (pin "24") (pinfunction "PIN24_24") (pintype "passive+no_connect"))
    )
  )
)
